# VSR_Mini_Mega_rev_1_206C_dual_led_option.net
KiCad netlist of a schematic drawn in EAGLE
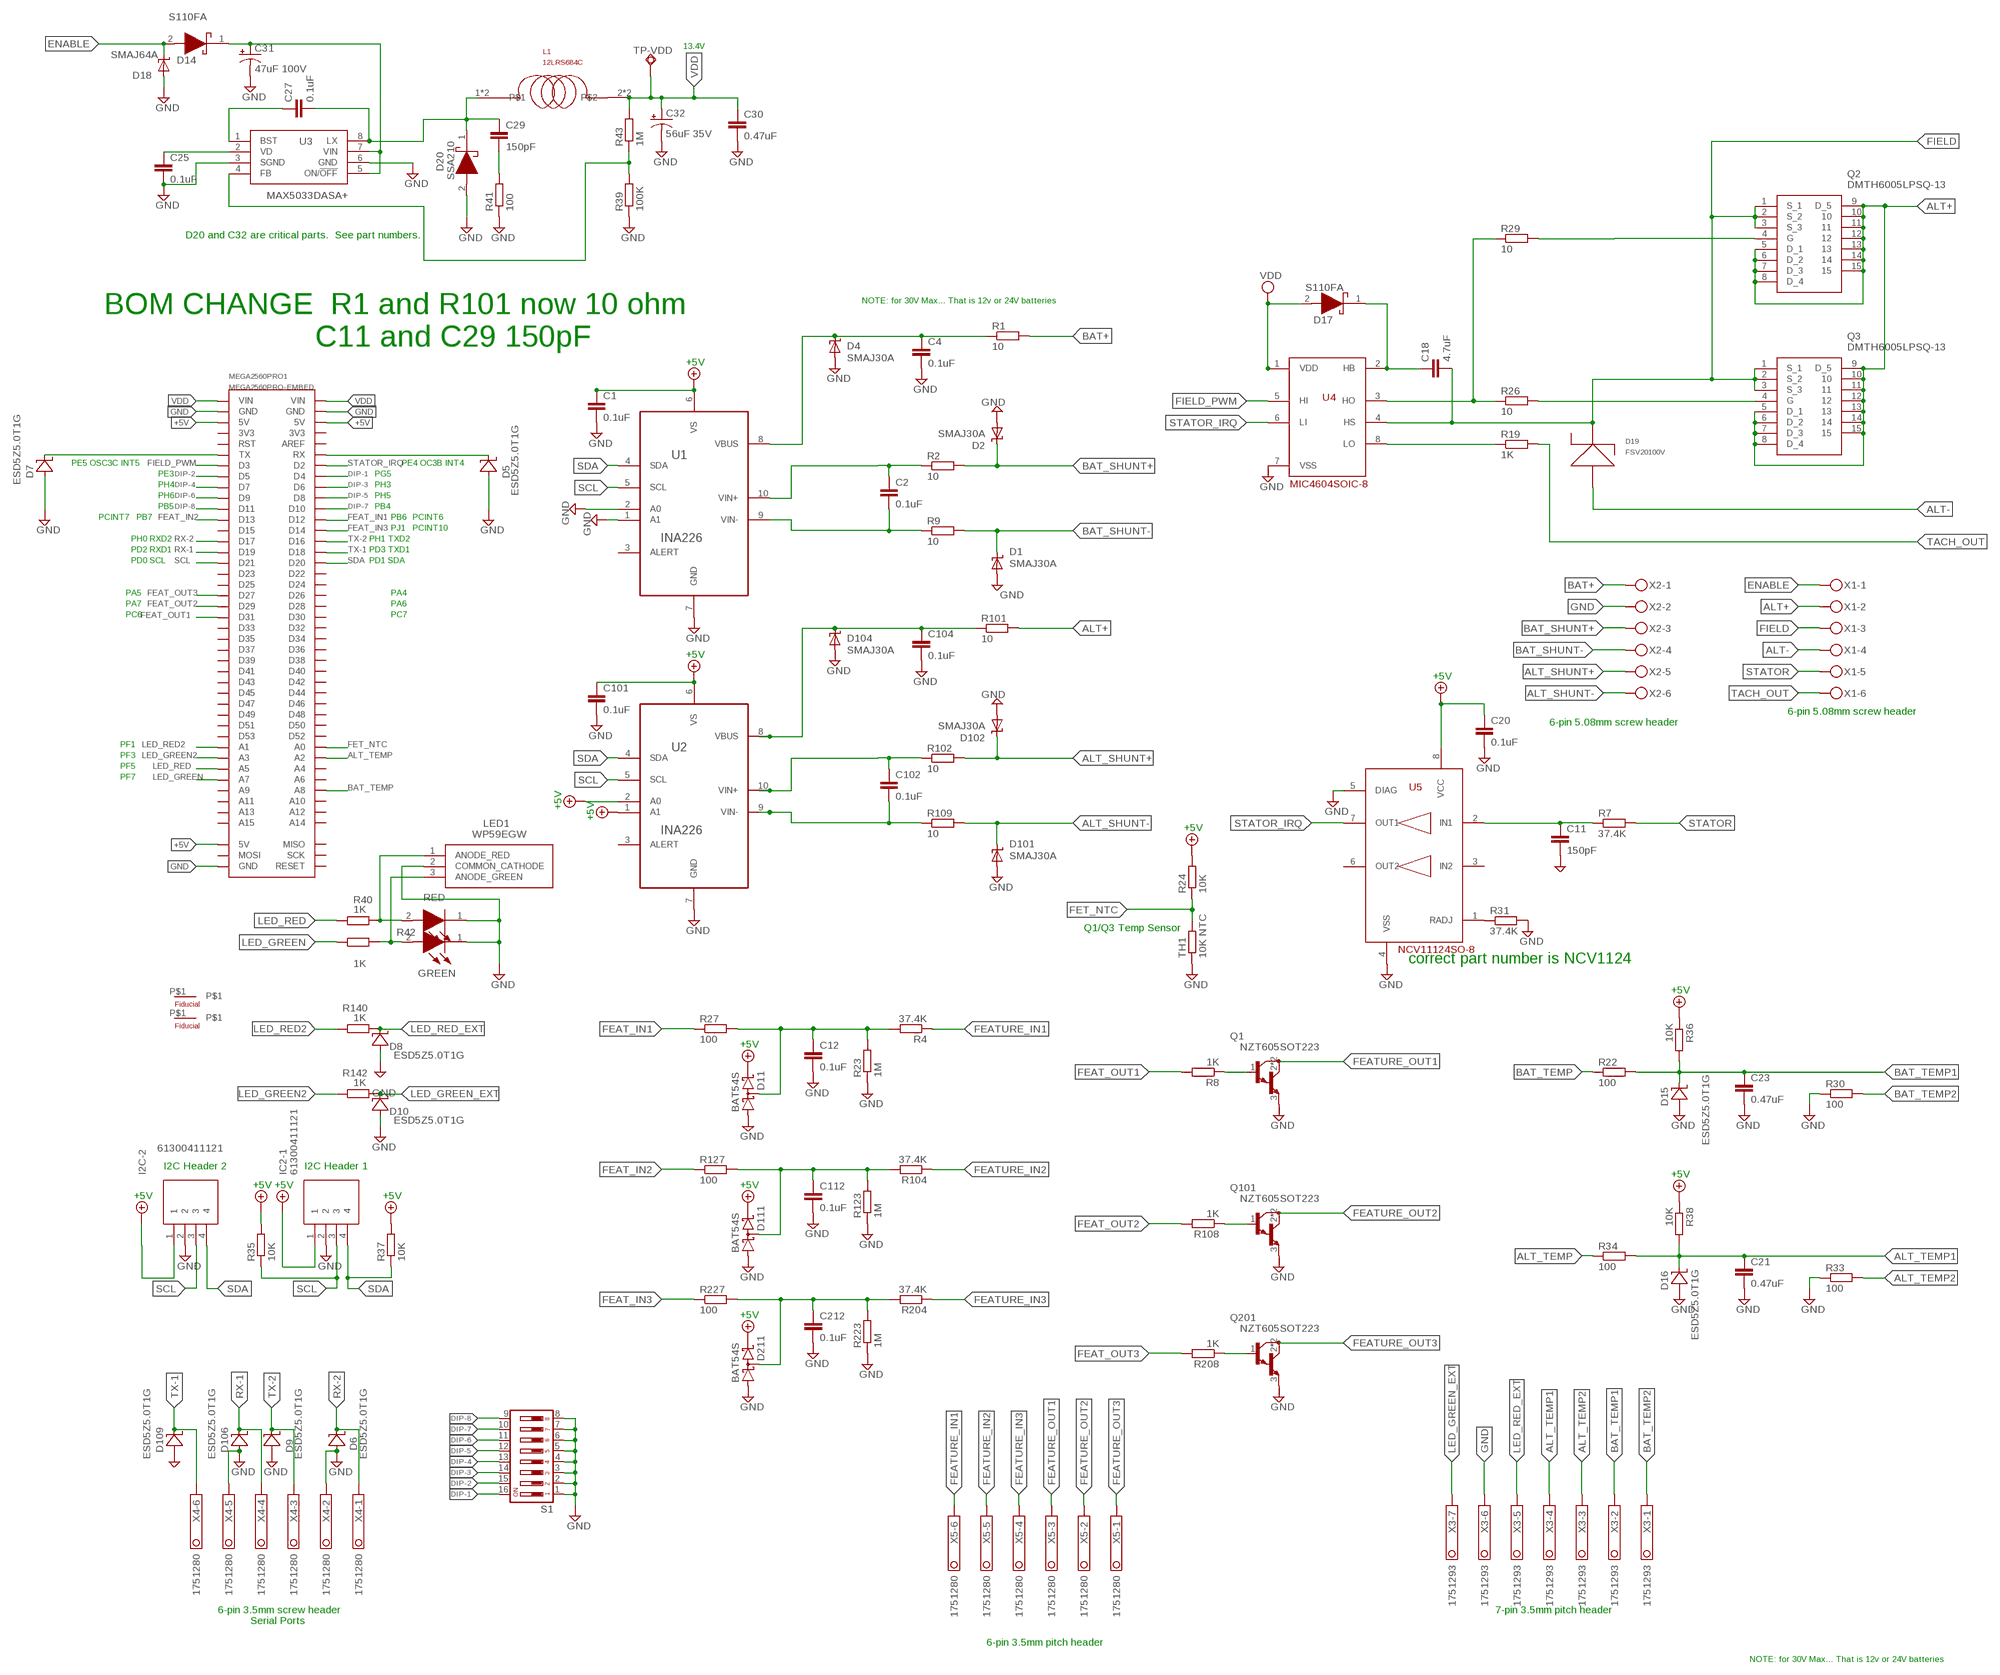
[diagram p0: schematic, sheet 1]

(export (version "E")
  (design (tool "Eeschema 10.0.6"))
  (components
    (comp (ref "C1")
      (value "0.1uF")
      (footprint "eagle-import:C0603")
      (libsource (lib "eagle-import") (part "C-EUC0603"))
    )
    (comp (ref "C2")
      (value "0.1uF")
      (footprint "eagle-import:C0603")
      (libsource (lib "eagle-import") (part "C-EUC0603"))
    )
    (comp (ref "C4")
      (value "0.1uF")
      (footprint "eagle-import:C0603")
      (libsource (lib "eagle-import") (part "C-EUC0603"))
    )
    (comp (ref "C11")
      (value "150pF")
      (footprint "eagle-import:C0603")
      (libsource (lib "eagle-import") (part "C-EUC0603"))
    )
    (comp (ref "C12")
      (value "0.1uF")
      (footprint "eagle-import:C0603")
      (libsource (lib "eagle-import") (part "C-EUC0603"))
    )
    (comp (ref "C18")
      (value "4.7uF")
      (footprint "eagle-import:C0603K")
      (libsource (lib "eagle-import") (part "C-EUC0603K"))
    )
    (comp (ref "C20")
      (value "0.1uF")
      (footprint "eagle-import:C0603")
      (libsource (lib "eagle-import") (part "C-EUC0603"))
    )
    (comp (ref "C21")
      (value "0.47uF")
      (footprint "eagle-import:C0603")
      (libsource (lib "eagle-import") (part "C-EUC0603"))
    )
    (comp (ref "C23")
      (value "0.47uF")
      (footprint "eagle-import:C0603")
      (libsource (lib "eagle-import") (part "C-EUC0603"))
    )
    (comp (ref "C25")
      (value "0.1uF")
      (footprint "eagle-import:C0603")
      (libsource (lib "eagle-import") (part "C-EUC0603"))
    )
    (comp (ref "C27")
      (value "0.1uF")
      (footprint "eagle-import:C0603")
      (libsource (lib "eagle-import") (part "C-EUC0603"))
    )
    (comp (ref "C29")
      (value "150pF")
      (footprint "eagle-import:C0603")
      (libsource (lib "eagle-import") (part "C-EUC0603"))
    )
    (comp (ref "C30")
      (value "0.47uF")
      (footprint "eagle-import:C0603")
      (libsource (lib "eagle-import") (part "C-EUC0603"))
    )
    (comp (ref "C31")
      (value "47uF 100V")
      (footprint "eagle-import:CAPPRD500W60D1000H1250B")
      (libsource (lib "eagle-import") (part "CPOL-USCAPPRD500W60D100H1250B"))
    )
    (comp (ref "C32")
      (value "56uF 35V")
      (footprint "eagle-import:CAPPRD250W50D630H1100B")
      (libsource (lib "eagle-import") (part "CPOL-US"))
    )
    (comp (ref "C101")
      (value "0.1uF")
      (footprint "eagle-import:C0603")
      (libsource (lib "eagle-import") (part "C-EUC0603"))
    )
    (comp (ref "C102")
      (value "0.1uF")
      (footprint "eagle-import:C0603")
      (libsource (lib "eagle-import") (part "C-EUC0603"))
    )
    (comp (ref "C104")
      (value "0.1uF")
      (footprint "eagle-import:C0603")
      (libsource (lib "eagle-import") (part "C-EUC0603"))
    )
    (comp (ref "C112")
      (value "0.1uF")
      (footprint "eagle-import:C0603")
      (libsource (lib "eagle-import") (part "C-EUC0603"))
    )
    (comp (ref "C212")
      (value "0.1uF")
      (footprint "eagle-import:C0603")
      (libsource (lib "eagle-import") (part "C-EUC0603"))
    )
    (comp (ref "D1")
      (value "SMAJ30A")
      (footprint "eagle-import:SMBJ")
      (libsource (lib "eagle-import") (part "SUPPRESSOR-SMBJ"))
    )
    (comp (ref "D2")
      (value "SMAJ30A")
      (footprint "eagle-import:SMBJ")
      (libsource (lib "eagle-import") (part "SUPPRESSOR-SMBJ"))
    )
    (comp (ref "D4")
      (value "SMAJ30A")
      (footprint "eagle-import:SMBJ")
      (libsource (lib "eagle-import") (part "SUPPRESSOR-SMBJ"))
    )
    (comp (ref "D5")
      (value "ESD5Z5.0T1G")
      (footprint "eagle-import:SOD523")
      (libsource (lib "eagle-import") (part "ESD5Z5.0T1G"))
    )
    (comp (ref "D6")
      (value "ESD5Z5.0T1G")
      (footprint "eagle-import:SOD523")
      (libsource (lib "eagle-import") (part "ESD5Z5.0T1G"))
    )
    (comp (ref "D7")
      (value "ESD5Z5.0T1G")
      (footprint "eagle-import:SOD523")
      (libsource (lib "eagle-import") (part "ESD5Z5.0T1G"))
    )
    (comp (ref "D8")
      (value "ESD5Z5.0T1G")
      (footprint "eagle-import:SOD523")
      (libsource (lib "eagle-import") (part "ESD5Z5.0T1G"))
    )
    (comp (ref "D9")
      (value "ESD5Z5.0T1G")
      (footprint "eagle-import:SOD523")
      (libsource (lib "eagle-import") (part "ESD5Z5.0T1G"))
    )
    (comp (ref "D10")
      (value "ESD5Z5.0T1G")
      (footprint "eagle-import:SOD523")
      (libsource (lib "eagle-import") (part "ESD5Z5.0T1G"))
    )
    (comp (ref "D11")
      (value "BAT54S")
      (footprint "eagle-import:SOT23")
      (libsource (lib "eagle-import") (part "BAT54S"))
    )
    (comp (ref "D14")
      (value "S110FA")
      (footprint "eagle-import:SODFL3618X143N")
      (fields (field (name "MOUSER_PART_NUMBER") "512-S110FA"))
      (libsource (lib "eagle-import") (part "S110FA"))
    )
    (comp (ref "D15")
      (value "ESD5Z5.0T1G")
      (footprint "eagle-import:SOD523")
      (libsource (lib "eagle-import") (part "ESD5Z5.0T1G"))
    )
    (comp (ref "D16")
      (value "ESD5Z5.0T1G")
      (footprint "eagle-import:SOD523")
      (libsource (lib "eagle-import") (part "ESD5Z5.0T1G"))
    )
    (comp (ref "D17")
      (value "S110FA")
      (footprint "eagle-import:SODFL3618X143N")
      (fields (field (name "MOUSER_PART_NUMBER") "512-S110FA"))
      (libsource (lib "eagle-import") (part "S110FA"))
    )
    (comp (ref "D18")
      (value "SMAJ64A")
      (footprint "eagle-import:SMBJ")
      (libsource (lib "eagle-import") (part "SUPPRESSOR-SMBJ"))
    )
    (comp (ref "D19")
      (value "FSV20100V")
      (footprint "eagle-import:TO-277")
      (fields (field (name "MF") "ON Semiconductor"))
      (libsource (lib "eagle-import") (part "FSV20100V"))
    )
    (comp (ref "D20")
      (value "SSA210")
      (footprint "eagle-import:DIOM5227X270N")
      (fields (field (name "MOUSER_PART_NUMBER") "512-SSA210"))
      (libsource (lib "eagle-import") (part "SSA210"))
    )
    (comp (ref "D101")
      (value "SMAJ30A")
      (footprint "eagle-import:SMBJ")
      (libsource (lib "eagle-import") (part "SUPPRESSOR-SMBJ"))
    )
    (comp (ref "D102")
      (value "SMAJ30A")
      (footprint "eagle-import:SMBJ")
      (libsource (lib "eagle-import") (part "SUPPRESSOR-SMBJ"))
    )
    (comp (ref "D104")
      (value "SMAJ30A")
      (footprint "eagle-import:SMBJ")
      (libsource (lib "eagle-import") (part "SUPPRESSOR-SMBJ"))
    )
    (comp (ref "D106")
      (value "ESD5Z5.0T1G")
      (footprint "eagle-import:SOD523")
      (libsource (lib "eagle-import") (part "ESD5Z5.0T1G"))
    )
    (comp (ref "D109")
      (value "ESD5Z5.0T1G")
      (footprint "eagle-import:SOD523")
      (libsource (lib "eagle-import") (part "ESD5Z5.0T1G"))
    )
    (comp (ref "D111")
      (value "BAT54S")
      (footprint "eagle-import:SOT23")
      (libsource (lib "eagle-import") (part "BAT54S"))
    )
    (comp (ref "D211")
      (value "BAT54S")
      (footprint "eagle-import:SOT23")
      (libsource (lib "eagle-import") (part "BAT54S"))
    )
    (comp (ref "FIDUCIAL1")
      (value "FIDUCIAL060")
      (footprint "eagle-import:FIDUCIAL060")
      (libsource (lib "eagle-import") (part "FIDUCIAL060"))
    )
    (comp (ref "FIDUCIAL2")
      (value "FIDUCIAL060")
      (footprint "eagle-import:FIDUCIAL060")
      (libsource (lib "eagle-import") (part "FIDUCIAL060"))
    )
    (comp (ref "GREEN")
      (value "599-0110-007F")
      (footprint "eagle-import:LEDM2012X90N")
      (fields (field (name "MOUSER_PART_NUMBER") "645-599-0110-007F"))
      (libsource (lib "eagle-import") (part "599-0110-007F"))
    )
    (comp (ref "I2C-2")
      (value "61300411121")
      (footprint "eagle-import:HDRV4W95P0X254_1X4_1016X254X85")
      (fields (field (name "MOUSER_PART_NUMBER") "710-61300411121"))
      (libsource (lib "eagle-import") (part "61300411121"))
    )
    (comp (ref "IC2-1")
      (value "61300411121")
      (footprint "eagle-import:HDRV4W95P0X254_1X4_1016X254X85")
      (fields (field (name "MOUSER_PART_NUMBER") "710-61300411121"))
      (libsource (lib "eagle-import") (part "61300411121"))
    )
    (comp (ref "L1")
      (value "12LRS684C")
      (footprint "eagle-import:IND_12LRS156C")
      (libsource (lib "eagle-import") (part "12LRS684C"))
    )
    (comp (ref "LED1")
      (value "WP59EGW")
      (footprint "eagle-import:T-1_3_4(5MM)_BI-COLOR_INDICATO")
      (fields (field (name "MOUSER_PART_NUMBER") "604-WP59EGW"))
      (libsource (lib "eagle-import") (part "WP59EGW"))
    )
    (comp (ref "MEGA2560PRO1")
      (value "MEGA2560PRO-EMBED")
      (footprint "eagle-import:MEGA2560PRO-EMBED")
      (libsource (lib "eagle-import") (part "MEGA2560PRO-EMBED"))
    )
    (comp (ref "Q1")
      (value "NZT605SOT223")
      (footprint "eagle-import:SOT223")
      (libsource (lib "eagle-import") (part "NZT605SOT223"))
    )
    (comp (ref "Q2")
      (value "DMTH6005LPSQ-13")
      (footprint "eagle-import:DMTH6005LPSQ13")
      (fields (field (name "MOUSER_PART_NUMBER") "621-DMTH6005LPSQ-13"))
      (libsource (lib "eagle-import") (part "DMTH6005LPSQ-13"))
    )
    (comp (ref "Q3")
      (value "DMTH6005LPSQ-13")
      (footprint "eagle-import:DMTH6005LPSQ13")
      (fields (field (name "MOUSER_PART_NUMBER") "621-DMTH6005LPSQ-13"))
      (libsource (lib "eagle-import") (part "DMTH6005LPSQ-13"))
    )
    (comp (ref "Q101")
      (value "NZT605SOT223")
      (footprint "eagle-import:SOT223")
      (libsource (lib "eagle-import") (part "NZT605SOT223"))
    )
    (comp (ref "Q201")
      (value "NZT605SOT223")
      (footprint "eagle-import:SOT223")
      (libsource (lib "eagle-import") (part "NZT605SOT223"))
    )
    (comp (ref "R1")
      (value "10")
      (footprint "eagle-import:R0603")
      (libsource (lib "eagle-import") (part "R-EU_R0603"))
    )
    (comp (ref "R2")
      (value "10")
      (footprint "eagle-import:R0603")
      (libsource (lib "eagle-import") (part "R-EU_R0603"))
    )
    (comp (ref "R4")
      (value "37.4K")
      (footprint "eagle-import:R0603")
      (libsource (lib "eagle-import") (part "R-EU_R0603"))
    )
    (comp (ref "R7")
      (value "37.4K")
      (footprint "eagle-import:R0603")
      (libsource (lib "eagle-import") (part "R-EU_R0603"))
    )
    (comp (ref "R8")
      (value "1K")
      (footprint "eagle-import:R0603")
      (libsource (lib "eagle-import") (part "R-EU_R0603"))
    )
    (comp (ref "R9")
      (value "10")
      (footprint "eagle-import:R0603")
      (libsource (lib "eagle-import") (part "R-EU_R0603"))
    )
    (comp (ref "R19")
      (value "1K")
      (footprint "eagle-import:R0603")
      (libsource (lib "eagle-import") (part "R-EU_R0603"))
    )
    (comp (ref "R22")
      (value "100")
      (footprint "eagle-import:R0603")
      (libsource (lib "eagle-import") (part "R-EU_R0603"))
    )
    (comp (ref "R23")
      (value "1M")
      (footprint "eagle-import:R0603")
      (libsource (lib "eagle-import") (part "R-EU_R0603"))
    )
    (comp (ref "R24")
      (value "10K")
      (footprint "eagle-import:R0603")
      (libsource (lib "eagle-import") (part "R-EU_R0603"))
    )
    (comp (ref "R26")
      (value "10")
      (footprint "eagle-import:R0603")
      (libsource (lib "eagle-import") (part "R-EU_R0603"))
    )
    (comp (ref "R27")
      (value "100")
      (footprint "eagle-import:R0603")
      (libsource (lib "eagle-import") (part "R-EU_R0603"))
    )
    (comp (ref "R29")
      (value "10")
      (footprint "eagle-import:R0603")
      (libsource (lib "eagle-import") (part "R-EU_R0603"))
    )
    (comp (ref "R30")
      (value "100")
      (footprint "eagle-import:R0603")
      (libsource (lib "eagle-import") (part "R-EU_R0603"))
    )
    (comp (ref "R31")
      (value "37.4K")
      (footprint "eagle-import:R0603")
      (libsource (lib "eagle-import") (part "R-EU_R0603"))
    )
    (comp (ref "R33")
      (value "100")
      (footprint "eagle-import:R0603")
      (libsource (lib "eagle-import") (part "R-EU_R0603"))
    )
    (comp (ref "R34")
      (value "100")
      (footprint "eagle-import:R0603")
      (libsource (lib "eagle-import") (part "R-EU_R0603"))
    )
    (comp (ref "R35")
      (value "10K")
      (footprint "eagle-import:R0603")
      (libsource (lib "eagle-import") (part "R-EU_R0603"))
    )
    (comp (ref "R36")
      (value "10K")
      (footprint "eagle-import:R0603")
      (libsource (lib "eagle-import") (part "R-EU_R0603"))
    )
    (comp (ref "R37")
      (value "10K")
      (footprint "eagle-import:R0603")
      (libsource (lib "eagle-import") (part "R-EU_R0603"))
    )
    (comp (ref "R38")
      (value "10K")
      (footprint "eagle-import:R0603")
      (libsource (lib "eagle-import") (part "R-EU_R0603"))
    )
    (comp (ref "R39")
      (value "100K")
      (footprint "eagle-import:R0603")
      (libsource (lib "eagle-import") (part "R-EU_R0603"))
    )
    (comp (ref "R40")
      (value "1K")
      (footprint "eagle-import:R0603")
      (libsource (lib "eagle-import") (part "R-EU_R0603"))
    )
    (comp (ref "R41")
      (value "100")
      (footprint "eagle-import:R0603")
      (libsource (lib "eagle-import") (part "R-EU_R0603"))
    )
    (comp (ref "R42")
      (value "1K")
      (footprint "eagle-import:R0603")
      (libsource (lib "eagle-import") (part "R-EU_R0603"))
    )
    (comp (ref "R43")
      (value "1M")
      (footprint "eagle-import:R0603")
      (libsource (lib "eagle-import") (part "R-EU_R0603"))
    )
    (comp (ref "R101")
      (value "10")
      (footprint "eagle-import:R0603")
      (libsource (lib "eagle-import") (part "R-EU_R0603"))
    )
    (comp (ref "R102")
      (value "10")
      (footprint "eagle-import:R0603")
      (libsource (lib "eagle-import") (part "R-EU_R0603"))
    )
    (comp (ref "R104")
      (value "37.4K")
      (footprint "eagle-import:R0603")
      (libsource (lib "eagle-import") (part "R-EU_R0603"))
    )
    (comp (ref "R108")
      (value "1K")
      (footprint "eagle-import:R0603")
      (libsource (lib "eagle-import") (part "R-EU_R0603"))
    )
    (comp (ref "R109")
      (value "10")
      (footprint "eagle-import:R0603")
      (libsource (lib "eagle-import") (part "R-EU_R0603"))
    )
    (comp (ref "R123")
      (value "1M")
      (footprint "eagle-import:R0603")
      (libsource (lib "eagle-import") (part "R-EU_R0603"))
    )
    (comp (ref "R127")
      (value "100")
      (footprint "eagle-import:R0603")
      (libsource (lib "eagle-import") (part "R-EU_R0603"))
    )
    (comp (ref "R140")
      (value "1K")
      (footprint "eagle-import:R0603")
      (libsource (lib "eagle-import") (part "R-EU_R0603"))
    )
    (comp (ref "R142")
      (value "1K")
      (footprint "eagle-import:R0603")
      (libsource (lib "eagle-import") (part "R-EU_R0603"))
    )
    (comp (ref "R204")
      (value "37.4K")
      (footprint "eagle-import:R0603")
      (libsource (lib "eagle-import") (part "R-EU_R0603"))
    )
    (comp (ref "R208")
      (value "1K")
      (footprint "eagle-import:R0603")
      (libsource (lib "eagle-import") (part "R-EU_R0603"))
    )
    (comp (ref "R223")
      (value "1M")
      (footprint "eagle-import:R0603")
      (libsource (lib "eagle-import") (part "R-EU_R0603"))
    )
    (comp (ref "R227")
      (value "100")
      (footprint "eagle-import:R0603")
      (libsource (lib "eagle-import") (part "R-EU_R0603"))
    )
    (comp (ref "RED")
      (value "599-0110-007F")
      (footprint "eagle-import:LEDM2012X90N")
      (fields (field (name "MOUSER_PART_NUMBER") "645-599-0110-007F"))
      (libsource (lib "eagle-import") (part "599-0110-007F"))
    )
    (comp (ref "S1")
      (value "DP08")
      (footprint "eagle-import:DP-08")
      (libsource (lib "eagle-import") (part "DP08"))
    )
    (comp (ref "TH1")
      (value "10K NTC")
      (footprint "eagle-import:R0402")
      (libsource (lib "eagle-import") (part "R-EU_R0402"))
    )
    (comp (ref "TP-VDD")
      (value "TPSQTP20SQ")
      (footprint "eagle-import:TP20SQ")
      (libsource (lib "eagle-import") (part "TPSQTP20SQ"))
    )
    (comp (ref "U1")
      (value "INA226")
      (footprint "eagle-import:SOP50P490X110-10N")
      (fields (field (name "MPN") "INA226AIDGSR"))
      (libsource (lib "eagle-import") (part "INA226"))
    )
    (comp (ref "U2")
      (value "INA226")
      (footprint "eagle-import:SOP50P490X110-10N")
      (fields (field (name "MPN") "INA226AIDGSR"))
      (libsource (lib "eagle-import") (part "INA226"))
    )
    (comp (ref "U3")
      (value "MAX5033DASA+")
      (footprint "eagle-import:SOIC127P600X175-8N")
      (fields (field (name "MOUSER_PART_NUMBER") "700-MAX5033DASA"))
      (libsource (lib "eagle-import") (part "MAX5033DASA+"))
    )
    (comp (ref "U4")
      (value "MIC4604SOIC-8")
      (footprint "eagle-import:SOIC8")
      (libsource (lib "eagle-import") (part "MIC4604SOIC-8"))
    )
    (comp (ref "U5")
      (value "NCV11124SO-8")
      (footprint "eagle-import:SO-8")
      (libsource (lib "eagle-import") (part "NCV11124SO-8"))
    )
    (comp (ref "X1")
      (value "MKDSN1,5/6-5,08")
      (footprint "eagle-import:MKDSN1,5_6-5,08")
      (libsource (lib "eagle-import") (part "MKDSN1,5/6-5,08"))
    )
    (comp (ref "X2")
      (value "MKDSN1,5/6-5,08")
      (footprint "eagle-import:MKDSN1,5_6-5,08")
      (libsource (lib "eagle-import") (part "MKDSN1,5/6-5,08"))
    )
    (comp (ref "X3")
      (value "1751293")
      (footprint "eagle-import:1751293")
      (libsource (lib "eagle-import") (part "1751293"))
    )
    (comp (ref "X4")
      (value "1751280")
      (footprint "eagle-import:1751280")
      (libsource (lib "eagle-import") (part "1751280"))
    )
    (comp (ref "X5")
      (value "1751280")
      (footprint "eagle-import:1751280")
      (libsource (lib "eagle-import") (part "1751280"))
    )
  )
  (nets
    (net (code "1") (name "+5V") (class "Default")
      (node (ref "C1") (pin "1") (pinfunction "1_1") (pintype "passive"))
      (node (ref "C101") (pin "1") (pinfunction "1_1") (pintype "passive"))
      (node (ref "C20") (pin "1") (pinfunction "1_1") (pintype "passive"))
      (node (ref "D11") (pin "2") (pinfunction "C2_2") (pintype "passive"))
      (node (ref "D111") (pin "2") (pinfunction "C2_2") (pintype "passive"))
      (node (ref "D211") (pin "2") (pinfunction "C2_2") (pintype "passive"))
      (node (ref "I2C-2") (pin "1") (pinfunction "1_1") (pintype "bidirectional"))
      (node (ref "IC2-1") (pin "1") (pinfunction "1_1") (pintype "bidirectional"))
      (node (ref "MEGA2560PRO1") (pin "5V@1") (pinfunction "5V_5V@1") (pintype "bidirectional"))
      (node (ref "MEGA2560PRO1") (pin "5V@2") (pinfunction "5V_5V@2") (pintype "bidirectional"))
      (node (ref "MEGA2560PRO1") (pin "5V@3") (pinfunction "5V_5V@3") (pintype "bidirectional"))
      (node (ref "R24") (pin "2") (pinfunction "2_2") (pintype "passive"))
      (node (ref "R35") (pin "2") (pinfunction "2_2") (pintype "passive"))
      (node (ref "R36") (pin "1") (pinfunction "1_1") (pintype "passive"))
      (node (ref "R37") (pin "2") (pinfunction "2_2") (pintype "passive"))
      (node (ref "R38") (pin "1") (pinfunction "1_1") (pintype "passive"))
      (node (ref "U1") (pin "6") (pinfunction "VS_6") (pintype "power_in"))
      (node (ref "U2") (pin "1") (pinfunction "A1_1") (pintype "input"))
      (node (ref "U2") (pin "2") (pinfunction "A0_2") (pintype "input"))
      (node (ref "U2") (pin "6") (pinfunction "VS_6") (pintype "power_in"))
      (node (ref "U5") (pin "8") (pinfunction "VCC_8") (pintype "bidirectional"))
    )
    (net (code "2") (name "ALT+") (class "Default")
      (node (ref "Q2") (pin "10") (pinfunction "10_10") (pintype "bidirectional"))
      (node (ref "Q2") (pin "11") (pinfunction "11_11") (pintype "bidirectional"))
      (node (ref "Q2") (pin "12") (pinfunction "12_12") (pintype "bidirectional"))
      (node (ref "Q2") (pin "13") (pinfunction "13_13") (pintype "bidirectional"))
      (node (ref "Q2") (pin "14") (pinfunction "14_14") (pintype "bidirectional"))
      (node (ref "Q2") (pin "15") (pinfunction "15_15") (pintype "bidirectional"))
      (node (ref "Q2") (pin "5") (pinfunction "D_1_5") (pintype "bidirectional"))
      (node (ref "Q2") (pin "6") (pinfunction "D_2_6") (pintype "bidirectional"))
      (node (ref "Q2") (pin "7") (pinfunction "D_3_7") (pintype "bidirectional"))
      (node (ref "Q2") (pin "8") (pinfunction "D_4_8") (pintype "bidirectional"))
      (node (ref "Q2") (pin "9") (pinfunction "D_5_9") (pintype "bidirectional"))
      (node (ref "Q3") (pin "10") (pinfunction "10_10") (pintype "bidirectional"))
      (node (ref "Q3") (pin "11") (pinfunction "11_11") (pintype "bidirectional"))
      (node (ref "Q3") (pin "12") (pinfunction "12_12") (pintype "bidirectional"))
      (node (ref "Q3") (pin "13") (pinfunction "13_13") (pintype "bidirectional"))
      (node (ref "Q3") (pin "14") (pinfunction "14_14") (pintype "bidirectional"))
      (node (ref "Q3") (pin "15") (pinfunction "15_15") (pintype "bidirectional"))
      (node (ref "Q3") (pin "5") (pinfunction "D_1_5") (pintype "bidirectional"))
      (node (ref "Q3") (pin "6") (pinfunction "D_2_6") (pintype "bidirectional"))
      (node (ref "Q3") (pin "7") (pinfunction "D_3_7") (pintype "bidirectional"))
      (node (ref "Q3") (pin "8") (pinfunction "D_4_8") (pintype "bidirectional"))
      (node (ref "Q3") (pin "9") (pinfunction "D_5_9") (pintype "bidirectional"))
      (node (ref "R101") (pin "2") (pinfunction "2_2") (pintype "passive"))
      (node (ref "X1") (pin "2") (pinfunction "KL_2") (pintype "passive"))
    )
    (net (code "3") (name "ALT-") (class "Default")
      (node (ref "D19") (pin "1") (pinfunction "P$2_1") (pintype "bidirectional"))
      (node (ref "D19") (pin "2") (pinfunction "P$2_2") (pintype "bidirectional"))
      (node (ref "X1") (pin "4") (pinfunction "KL_4") (pintype "passive"))
    )
    (net (code "4") (name "ALT_SHUNT+") (class "Default")
      (node (ref "D102") (pin "C") (pinfunction "C_C") (pintype "passive"))
      (node (ref "R102") (pin "2") (pinfunction "2_2") (pintype "passive"))
      (node (ref "X2") (pin "5") (pinfunction "KL_5") (pintype "passive"))
    )
    (net (code "5") (name "ALT_SHUNT-") (class "Default")
      (node (ref "D101") (pin "C") (pinfunction "C_C") (pintype "passive"))
      (node (ref "R109") (pin "2") (pinfunction "2_2") (pintype "passive"))
      (node (ref "X2") (pin "6") (pinfunction "KL_6") (pintype "passive"))
    )
    (net (code "6") (name "ALT_TEMP") (class "Default")
      (node (ref "MEGA2560PRO1") (pin "A2") (pinfunction "A2_A2") (pintype "bidirectional"))
      (node (ref "R34") (pin "1") (pinfunction "1_1") (pintype "passive"))
    )
    (net (code "7") (name "ALT_TEMP1") (class "Default")
      (node (ref "C21") (pin "1") (pinfunction "1_1") (pintype "passive"))
      (node (ref "D16") (pin "C") (pinfunction "C_C") (pintype "passive"))
      (node (ref "R34") (pin "2") (pinfunction "2_2") (pintype "passive"))
      (node (ref "R38") (pin "2") (pinfunction "2_2") (pintype "passive"))
      (node (ref "X3") (pin "4") (pinfunction "K_4") (pintype "passive"))
    )
    (net (code "8") (name "ALT_TEMP2") (class "Default")
      (node (ref "R33") (pin "2") (pinfunction "2_2") (pintype "passive"))
      (node (ref "X3") (pin "3") (pinfunction "K_3") (pintype "passive"))
    )
    (net (code "9") (name "BAT+") (class "Default")
      (node (ref "R1") (pin "2") (pinfunction "2_2") (pintype "passive"))
      (node (ref "X2") (pin "1") (pinfunction "KL_1") (pintype "passive"))
    )
    (net (code "10") (name "BAT_SHUNT+") (class "Default")
      (node (ref "D2") (pin "C") (pinfunction "C_C") (pintype "passive"))
      (node (ref "R2") (pin "2") (pinfunction "2_2") (pintype "passive"))
      (node (ref "X2") (pin "3") (pinfunction "KL_3") (pintype "passive"))
    )
    (net (code "11") (name "BAT_SHUNT-") (class "Default")
      (node (ref "D1") (pin "C") (pinfunction "C_C") (pintype "passive"))
      (node (ref "R9") (pin "2") (pinfunction "2_2") (pintype "passive"))
      (node (ref "X2") (pin "4") (pinfunction "KL_4") (pintype "passive"))
    )
    (net (code "12") (name "BAT_TEMP") (class "Default")
      (node (ref "MEGA2560PRO1") (pin "A8") (pinfunction "A8_A8") (pintype "bidirectional"))
      (node (ref "R22") (pin "1") (pinfunction "1_1") (pintype "passive"))
    )
    (net (code "13") (name "BAT_TEMP1") (class "Default")
      (node (ref "C23") (pin "1") (pinfunction "1_1") (pintype "passive"))
      (node (ref "D15") (pin "C") (pinfunction "C_C") (pintype "passive"))
      (node (ref "R22") (pin "2") (pinfunction "2_2") (pintype "passive"))
      (node (ref "R36") (pin "2") (pinfunction "2_2") (pintype "passive"))
      (node (ref "X3") (pin "2") (pinfunction "K_2") (pintype "passive"))
    )
    (net (code "14") (name "BAT_TEMP2") (class "Default")
      (node (ref "R30") (pin "2") (pinfunction "2_2") (pintype "passive"))
      (node (ref "X3") (pin "1") (pinfunction "K_1") (pintype "passive"))
    )
    (net (code "15") (name "DIP-1") (class "Default")
      (node (ref "MEGA2560PRO1") (pin "D4") (pinfunction "D4_D4") (pintype "bidirectional"))
      (node (ref "S1") (pin "16") (pinfunction "16_16") (pintype "passive"))
    )
    (net (code "16") (name "DIP-2") (class "Default")
      (node (ref "MEGA2560PRO1") (pin "D5") (pinfunction "D5_D5") (pintype "bidirectional"))
      (node (ref "S1") (pin "15") (pinfunction "15_15") (pintype "passive"))
    )
    (net (code "17") (name "DIP-3") (class "Default")
      (node (ref "MEGA2560PRO1") (pin "D6") (pinfunction "D6_D6") (pintype "bidirectional"))
      (node (ref "S1") (pin "14") (pinfunction "14_14") (pintype "passive"))
    )
    (net (code "18") (name "DIP-4") (class "Default")
      (node (ref "MEGA2560PRO1") (pin "D7") (pinfunction "D7_D7") (pintype "bidirectional"))
      (node (ref "S1") (pin "13") (pinfunction "13_13") (pintype "passive"))
    )
    (net (code "19") (name "DIP-5") (class "Default")
      (node (ref "MEGA2560PRO1") (pin "D8") (pinfunction "D8_D8") (pintype "bidirectional"))
      (node (ref "S1") (pin "12") (pinfunction "12_12") (pintype "passive"))
    )
    (net (code "20") (name "DIP-6") (class "Default")
      (node (ref "MEGA2560PRO1") (pin "D9") (pinfunction "D9_D9") (pintype "bidirectional"))
      (node (ref "S1") (pin "11") (pinfunction "11_11") (pintype "passive"))
    )
    (net (code "21") (name "DIP-7") (class "Default")
      (node (ref "MEGA2560PRO1") (pin "D10") (pinfunction "D10_D10") (pintype "bidirectional"))
      (node (ref "S1") (pin "10") (pinfunction "10_10") (pintype "passive"))
    )
    (net (code "22") (name "DIP-8") (class "Default")
      (node (ref "MEGA2560PRO1") (pin "D11") (pinfunction "D11_D11") (pintype "bidirectional"))
      (node (ref "S1") (pin "9") (pinfunction "9_9") (pintype "passive"))
    )
    (net (code "23") (name "ENABLE") (class "Default")
      (node (ref "D14") (pin "2") (pinfunction "A_2") (pintype "bidirectional"))
      (node (ref "D18") (pin "C") (pinfunction "C_C") (pintype "passive"))
      (node (ref "X1") (pin "1") (pinfunction "KL_1") (pintype "passive"))
    )
    (net (code "24") (name "FEATURE_IN1") (class "Default")
      (node (ref "R4") (pin "1") (pinfunction "1_1") (pintype "passive"))
      (node (ref "X5") (pin "6") (pinfunction "K_6") (pintype "passive"))
    )
    (net (code "25") (name "FEATURE_IN2") (class "Default")
      (node (ref "R104") (pin "1") (pinfunction "1_1") (pintype "passive"))
      (node (ref "X5") (pin "5") (pinfunction "K_5") (pintype "passive"))
    )
    (net (code "26") (name "FEATURE_IN3") (class "Default")
      (node (ref "R204") (pin "1") (pinfunction "1_1") (pintype "passive"))
      (node (ref "X5") (pin "4") (pinfunction "K_4") (pintype "passive"))
    )
    (net (code "27") (name "FEATURE_OUT1") (class "Default")
      (node (ref "Q1") (pin "2") (pinfunction "C_2") (pintype "passive"))
      (node (ref "Q1") (pin "4") (pinfunction "C_4") (pintype "passive"))
      (node (ref "X5") (pin "3") (pinfunction "K_3") (pintype "passive"))
    )
    (net (code "28") (name "FEATURE_OUT2") (class "Default")
      (node (ref "Q101") (pin "2") (pinfunction "C_2") (pintype "passive"))
      (node (ref "Q101") (pin "4") (pinfunction "C_4") (pintype "passive"))
      (node (ref "X5") (pin "2") (pinfunction "K_2") (pintype "passive"))
    )
    (net (code "29") (name "FEATURE_OUT3") (class "Default")
      (node (ref "Q201") (pin "2") (pinfunction "C_2") (pintype "passive"))
      (node (ref "Q201") (pin "4") (pinfunction "C_4") (pintype "passive"))
      (node (ref "X5") (pin "1") (pinfunction "K_1") (pintype "passive"))
    )
    (net (code "30") (name "FEAT_IN1") (class "Default")
      (node (ref "MEGA2560PRO1") (pin "D12") (pinfunction "D12_D12") (pintype "bidirectional"))
      (node (ref "R27") (pin "1") (pinfunction "1_1") (pintype "passive"))
    )
    (net (code "31") (name "FEAT_IN2") (class "Default")
      (node (ref "MEGA2560PRO1") (pin "D13") (pinfunction "D13_D13") (pintype "bidirectional"))
      (node (ref "R127") (pin "1") (pinfunction "1_1") (pintype "passive"))
    )
    (net (code "32") (name "FEAT_IN3") (class "Default")
      (node (ref "MEGA2560PRO1") (pin "D14") (pinfunction "D14_D14") (pintype "bidirectional"))
      (node (ref "R227") (pin "1") (pinfunction "1_1") (pintype "passive"))
    )
    (net (code "33") (name "FEAT_OUT1") (class "Default")
      (node (ref "MEGA2560PRO1") (pin "D31") (pinfunction "D31_D31") (pintype "bidirectional"))
      (node (ref "R8") (pin "2") (pinfunction "2_2") (pintype "passive"))
    )
    (net (code "34") (name "FEAT_OUT2") (class "Default")
      (node (ref "MEGA2560PRO1") (pin "D29") (pinfunction "D29_D29") (pintype "bidirectional"))
      (node (ref "R108") (pin "2") (pinfunction "2_2") (pintype "passive"))
    )
    (net (code "35") (name "FEAT_OUT3") (class "Default")
      (node (ref "MEGA2560PRO1") (pin "D27") (pinfunction "D27_D27") (pintype "bidirectional"))
      (node (ref "R208") (pin "2") (pinfunction "2_2") (pintype "passive"))
    )
    (net (code "36") (name "FET_NTC") (class "Default")
      (node (ref "MEGA2560PRO1") (pin "A0") (pinfunction "A0_A0") (pintype "bidirectional"))
      (node (ref "R24") (pin "1") (pinfunction "1_1") (pintype "passive"))
      (node (ref "TH1") (pin "2") (pinfunction "2_2") (pintype "passive"))
    )
    (net (code "37") (name "FIELD") (class "Default")
      (node (ref "C18") (pin "2") (pinfunction "2_2") (pintype "passive"))
      (node (ref "D19") (pin "3") (pinfunction "P$1_3") (pintype "bidirectional"))
      (node (ref "Q2") (pin "1") (pinfunction "S_1_1") (pintype "bidirectional"))
      (node (ref "Q2") (pin "2") (pinfunction "S_2_2") (pintype "bidirectional"))
      (node (ref "Q2") (pin "3") (pinfunction "S_3_3") (pintype "bidirectional"))
      (node (ref "Q3") (pin "1") (pinfunction "S_1_1") (pintype "bidirectional"))
      (node (ref "Q3") (pin "2") (pinfunction "S_2_2") (pintype "bidirectional"))
      (node (ref "Q3") (pin "3") (pinfunction "S_3_3") (pintype "bidirectional"))
      (node (ref "U4") (pin "4") (pinfunction "HS_4") (pintype "bidirectional"))
      (node (ref "X1") (pin "3") (pinfunction "KL_3") (pintype "passive"))
    )
    (net (code "38") (name "FIELD_PWM") (class "Default")
      (node (ref "MEGA2560PRO1") (pin "D3") (pinfunction "D3_D3") (pintype "bidirectional"))
      (node (ref "U4") (pin "5") (pinfunction "HI_5") (pintype "bidirectional"))
    )
    (net (code "39") (name "GND") (class "Default")
      (node (ref "C1") (pin "2") (pinfunction "2_2") (pintype "passive"))
      (node (ref "C101") (pin "2") (pinfunction "2_2") (pintype "passive"))
      (node (ref "C104") (pin "2") (pinfunction "2_2") (pintype "passive"))
      (node (ref "C11") (pin "2") (pinfunction "2_2") (pintype "passive"))
      (node (ref "C112") (pin "2") (pinfunction "2_2") (pintype "passive"))
      (node (ref "C12") (pin "2") (pinfunction "2_2") (pintype "passive"))
      (node (ref "C20") (pin "2") (pinfunction "2_2") (pintype "passive"))
      (node (ref "C21") (pin "2") (pinfunction "2_2") (pintype "passive"))
      (node (ref "C212") (pin "2") (pinfunction "2_2") (pintype "passive"))
      (node (ref "C23") (pin "2") (pinfunction "2_2") (pintype "passive"))
      (node (ref "C25") (pin "2") (pinfunction "2_2") (pintype "passive"))
      (node (ref "C30") (pin "2") (pinfunction "2_2") (pintype "passive"))
      (node (ref "C31") (pin "2") (pinfunction "-_2") (pintype "passive"))
      (node (ref "C32") (pin "2") (pinfunction "-_2") (pintype "passive"))
      (node (ref "C4") (pin "2") (pinfunction "2_2") (pintype "passive"))
      (node (ref "D1") (pin "A") (pinfunction "A_A") (pintype "passive"))
      (node (ref "D10") (pin "A") (pinfunction "A_A") (pintype "passive"))
      (node (ref "D101") (pin "A") (pinfunction "A_A") (pintype "passive"))
      (node (ref "D102") (pin "A") (pinfunction "A_A") (pintype "passive"))
      (node (ref "D104") (pin "A") (pinfunction "A_A") (pintype "passive"))
      (node (ref "D106") (pin "A") (pinfunction "A_A") (pintype "passive"))
      (node (ref "D109") (pin "A") (pinfunction "A_A") (pintype "passive"))
      (node (ref "D11") (pin "1") (pinfunction "A1_1") (pintype "passive"))
      (node (ref "D111") (pin "1") (pinfunction "A1_1") (pintype "passive"))
      (node (ref "D15") (pin "A") (pinfunction "A_A") (pintype "passive"))
      (node (ref "D16") (pin "A") (pinfunction "A_A") (pintype "passive"))
      (node (ref "D18") (pin "A") (pinfunction "A_A") (pintype "passive"))
      (node (ref "D2") (pin "A") (pinfunction "A_A") (pintype "passive"))
      (node (ref "D20") (pin "2") (pinfunction "A_2") (pintype "bidirectional"))
      (node (ref "D211") (pin "1") (pinfunction "A1_1") (pintype "passive"))
      (node (ref "D4") (pin "A") (pinfunction "A_A") (pintype "passive"))
      (node (ref "D5") (pin "A") (pinfunction "A_A") (pintype "passive"))
      (node (ref "D6") (pin "A") (pinfunction "A_A") (pintype "passive"))
      (node (ref "D7") (pin "A") (pinfunction "A_A") (pintype "passive"))
      (node (ref "D8") (pin "A") (pinfunction "A_A") (pintype "passive"))
      (node (ref "D9") (pin "A") (pinfunction "A_A") (pintype "passive"))
      (node (ref "GREEN") (pin "1") (pinfunction "K_1") (pintype "bidirectional"))
      (node (ref "I2C-2") (pin "2") (pinfunction "2_2") (pintype "bidirectional"))
      (node (ref "IC2-1") (pin "2") (pinfunction "2_2") (pintype "bidirectional"))
      (node (ref "LED1") (pin "2") (pinfunction "COMMON_CATHODE_2") (pintype "bidirectional"))
      (node (ref "MEGA2560PRO1") (pin "GND@1") (pinfunction "GND_GND@1") (pintype "bidirectional"))
      (node (ref "MEGA2560PRO1") (pin "GND@2") (pinfunction "GND_GND@2") (pintype "bidirectional"))
      (node (ref "MEGA2560PRO1") (pin "GND@3") (pinfunction "GND_GND@3") (pintype "bidirectional"))
      (node (ref "Q1") (pin "3") (pinfunction "E_3") (pintype "passive"))
      (node (ref "Q101") (pin "3") (pinfunction "E_3") (pintype "passive"))
      (node (ref "Q201") (pin "3") (pinfunction "E_3") (pintype "passive"))
      (node (ref "R123") (pin "1") (pinfunction "1_1") (pintype "passive"))
      (node (ref "R223") (pin "1") (pinfunction "1_1") (pintype "passive"))
      (node (ref "R23") (pin "1") (pinfunction "1_1") (pintype "passive"))
      (node (ref "R30") (pin "1") (pinfunction "1_1") (pintype "passive"))
      (node (ref "R31") (pin "2") (pinfunction "2_2") (pintype "passive"))
      (node (ref "R33") (pin "1") (pinfunction "1_1") (pintype "passive"))
      (node (ref "R39") (pin "1") (pinfunction "1_1") (pintype "passive"))
      (node (ref "R41") (pin "1") (pinfunction "1_1") (pintype "passive"))
      (node (ref "RED") (pin "1") (pinfunction "K_1") (pintype "bidirectional"))
      (node (ref "S1") (pin "1") (pinfunction "1_1") (pintype "passive"))
      (node (ref "S1") (pin "2") (pinfunction "2_2") (pintype "passive"))
      (node (ref "S1") (pin "3") (pinfunction "3_3") (pintype "passive"))
      (node (ref "S1") (pin "4") (pinfunction "4_4") (pintype "passive"))
      (node (ref "S1") (pin "5") (pinfunction "5_5") (pintype "passive"))
      (node (ref "S1") (pin "6") (pinfunction "6_6") (pintype "passive"))
      (node (ref "S1") (pin "7") (pinfunction "7_7") (pintype "passive"))
      (node (ref "S1") (pin "8") (pinfunction "8_8") (pintype "passive"))
      (node (ref "TH1") (pin "1") (pinfunction "1_1") (pintype "passive"))
      (node (ref "U1") (pin "1") (pinfunction "A1_1") (pintype "input"))
      (node (ref "U1") (pin "2") (pinfunction "A0_2") (pintype "input"))
      (node (ref "U1") (pin "7") (pinfunction "GND_7") (pintype "passive"))
      (node (ref "U2") (pin "7") (pinfunction "GND_7") (pintype "passive"))
      (node (ref "U3") (pin "3") (pinfunction "SGND_3") (pintype "bidirectional"))
      (node (ref "U3") (pin "6") (pinfunction "GND_6") (pintype "bidirectional"))
      (node (ref "U4") (pin "7") (pinfunction "VSS_7") (pintype "bidirectional"))
      (node (ref "U5") (pin "4") (pinfunction "VSS_4") (pintype "bidirectional"))
      (node (ref "U5") (pin "5") (pinfunction "DIAG_5") (pintype "bidirectional"))
      (node (ref "X2") (pin "2") (pinfunction "KL_2") (pintype "passive"))
      (node (ref "X3") (pin "6") (pinfunction "K_6") (pintype "passive"))
      (node (ref "X4") (pin "2") (pinfunction "K_2") (pintype "passive"))
      (node (ref "X4") (pin "5") (pinfunction "K_5") (pintype "passive"))
    )
    (net (code "40") (name "LED_GREEN") (class "Default")
      (node (ref "MEGA2560PRO1") (pin "A7") (pinfunction "A7_A7") (pintype "bidirectional"))
      (node (ref "R42") (pin "1") (pinfunction "1_1") (pintype "passive"))
    )
    (net (code "41") (name "LED_GREEN2") (class "Default")
      (node (ref "MEGA2560PRO1") (pin "A3") (pinfunction "A3_A3") (pintype "bidirectional"))
      (node (ref "R142") (pin "1") (pinfunction "1_1") (pintype "passive"))
    )
    (net (code "42") (name "LED_GREEN_EXT") (class "Default")
      (node (ref "D10") (pin "C") (pinfunction "C_C") (pintype "passive"))
      (node (ref "R142") (pin "2") (pinfunction "2_2") (pintype "passive"))
      (node (ref "X3") (pin "7") (pinfunction "K_7") (pintype "passive"))
    )
    (net (code "43") (name "LED_RED") (class "Default")
      (node (ref "MEGA2560PRO1") (pin "A5") (pinfunction "A5_A5") (pintype "bidirectional"))
      (node (ref "R40") (pin "1") (pinfunction "1_1") (pintype "passive"))
    )
    (net (code "44") (name "LED_RED2") (class "Default")
      (node (ref "MEGA2560PRO1") (pin "A1") (pinfunction "A1_A1") (pintype "bidirectional"))
      (node (ref "R140") (pin "1") (pinfunction "1_1") (pintype "passive"))
    )
    (net (code "45") (name "LED_RED_EXT") (class "Default")
      (node (ref "D8") (pin "C") (pinfunction "C_C") (pintype "passive"))
      (node (ref "R140") (pin "2") (pinfunction "2_2") (pintype "passive"))
      (node (ref "X3") (pin "5") (pinfunction "K_5") (pintype "passive"))
    )
    (net (code "46") (name "Net-(C29-Pad2)") (class "Default")
      (node (ref "C29") (pin "2") (pinfunction "2_2") (pintype "passive"))
      (node (ref "R41") (pin "2") (pinfunction "2_2") (pintype "passive"))
    )
    (net (code "47") (name "Net-(C31-+)") (class "Default")
      (node (ref "C31") (pin "1") (pinfunction "+_1") (pintype "passive"))
      (node (ref "D14") (pin "1") (pinfunction "K_1") (pintype "bidirectional"))
      (node (ref "U3") (pin "5") (pinfunction "ON/~{OFF}_5") (pintype "bidirectional"))
      (node (ref "U3") (pin "7") (pinfunction "VIN_7") (pintype "bidirectional"))
    )
    (net (code "48") (name "Net-(D5-PadC)") (class "Default")
      (node (ref "D5") (pin "C") (pinfunction "C_C") (pintype "passive"))
      (node (ref "MEGA2560PRO1") (pin "RX") (pinfunction "RX_RX") (pintype "bidirectional"))
    )
    (net (code "49") (name "Net-(D7-PadC)") (class "Default")
      (node (ref "D7") (pin "C") (pinfunction "C_C") (pintype "passive"))
      (node (ref "MEGA2560PRO1") (pin "TX") (pinfunction "TX_TX") (pintype "bidirectional"))
    )
    (net (code "50") (name "Net-(D11-C1A2)") (class "Default")
      (node (ref "C12") (pin "1") (pinfunction "1_1") (pintype "passive"))
      (node (ref "D11") (pin "3") (pinfunction "C1A2_3") (pintype "passive"))
      (node (ref "R23") (pin "2") (pinfunction "2_2") (pintype "passive"))
      (node (ref "R27") (pin "2") (pinfunction "2_2") (pintype "passive"))
      (node (ref "R4") (pin "2") (pinfunction "2_2") (pintype "passive"))
    )
    (net (code "51") (name "Net-(D17-K)") (class "Default")
      (node (ref "C18") (pin "1") (pinfunction "1_1") (pintype "passive"))
      (node (ref "D17") (pin "1") (pinfunction "K_1") (pintype "bidirectional"))
      (node (ref "U4") (pin "2") (pinfunction "HB_2") (pintype "bidirectional"))
    )
    (net (code "52") (name "Net-(D20-K)") (class "Default")
      (node (ref "C27") (pin "2") (pinfunction "2_2") (pintype "passive"))
      (node (ref "C29") (pin "1") (pinfunction "1_1") (pintype "passive"))
      (node (ref "D20") (pin "1") (pinfunction "K_1") (pintype "bidirectional"))
      (node (ref "L1") (pin "1") (pinfunction "P$1_1") (pintype "bidirectional"))
      (node (ref "L1") (pin "4") (pinfunction "P$1_4") (pintype "bidirectional"))
      (node (ref "U3") (pin "8") (pinfunction "LX_8") (pintype "bidirectional"))
    )
    (net (code "53") (name "Net-(D111-C1A2)") (class "Default")
      (node (ref "C112") (pin "1") (pinfunction "1_1") (pintype "passive"))
      (node (ref "D111") (pin "3") (pinfunction "C1A2_3") (pintype "passive"))
      (node (ref "R104") (pin "2") (pinfunction "2_2") (pintype "passive"))
      (node (ref "R123") (pin "2") (pinfunction "2_2") (pintype "passive"))
      (node (ref "R127") (pin "2") (pinfunction "2_2") (pintype "passive"))
    )
    (net (code "54") (name "Net-(D211-C1A2)") (class "Default")
      (node (ref "C212") (pin "1") (pinfunction "1_1") (pintype "passive"))
      (node (ref "D211") (pin "3") (pinfunction "C1A2_3") (pintype "passive"))
      (node (ref "R204") (pin "2") (pinfunction "2_2") (pintype "passive"))
      (node (ref "R223") (pin "2") (pinfunction "2_2") (pintype "passive"))
      (node (ref "R227") (pin "2") (pinfunction "2_2") (pintype "passive"))
    )
    (net (code "55") (name "Net-(GREEN-A)") (class "Default")
      (node (ref "GREEN") (pin "2") (pinfunction "A_2") (pintype "bidirectional"))
      (node (ref "LED1") (pin "3") (pinfunction "ANODE_GREEN_3") (pintype "bidirectional"))
      (node (ref "R42") (pin "2") (pinfunction "2_2") (pintype "passive"))
    )
    (net (code "56") (name "Net-(LED1-ANODE_RED)") (class "Default")
      (node (ref "LED1") (pin "1") (pinfunction "ANODE_RED_1") (pintype "bidirectional"))
      (node (ref "R40") (pin "2") (pinfunction "2_2") (pintype "passive"))
      (node (ref "RED") (pin "2") (pinfunction "A_2") (pintype "bidirectional"))
    )
    (net (code "57") (name "Net-(Q1-B)") (class "Default")
      (node (ref "Q1") (pin "1") (pinfunction "B_1") (pintype "passive"))
      (node (ref "R8") (pin "1") (pinfunction "1_1") (pintype "passive"))
    )
    (net (code "58") (name "Net-(Q2-G)") (class "Default")
      (node (ref "Q2") (pin "4") (pinfunction "G_4") (pintype "bidirectional"))
      (node (ref "R29") (pin "2") (pinfunction "2_2") (pintype "passive"))
    )
    (net (code "59") (name "Net-(Q3-G)") (class "Default")
      (node (ref "Q3") (pin "4") (pinfunction "G_4") (pintype "bidirectional"))
      (node (ref "R26") (pin "2") (pinfunction "2_2") (pintype "passive"))
    )
    (net (code "60") (name "Net-(Q101-B)") (class "Default")
      (node (ref "Q101") (pin "1") (pinfunction "B_1") (pintype "passive"))
      (node (ref "R108") (pin "1") (pinfunction "1_1") (pintype "passive"))
    )
    (net (code "61") (name "Net-(Q201-B)") (class "Default")
      (node (ref "Q201") (pin "1") (pinfunction "B_1") (pintype "passive"))
      (node (ref "R208") (pin "1") (pinfunction "1_1") (pintype "passive"))
    )
    (net (code "62") (name "Net-(U1-VBUS)") (class "Default")
      (node (ref "C4") (pin "1") (pinfunction "1_1") (pintype "passive"))
      (node (ref "D4") (pin "C") (pinfunction "C_C") (pintype "passive"))
      (node (ref "R1") (pin "1") (pinfunction "1_1") (pintype "passive"))
      (node (ref "U1") (pin "8") (pinfunction "VBUS_8") (pintype "input"))
    )
    (net (code "63") (name "Net-(U1-VIN+)") (class "Default")
      (node (ref "C2") (pin "1") (pinfunction "1_1") (pintype "passive"))
      (node (ref "R2") (pin "1") (pinfunction "1_1") (pintype "passive"))
      (node (ref "U1") (pin "10") (pinfunction "VIN+_10") (pintype "power_in"))
    )
    (net (code "64") (name "Net-(U1-VIN-)") (class "Default")
      (node (ref "C2") (pin "2") (pinfunction "2_2") (pintype "passive"))
      (node (ref "R9") (pin "1") (pinfunction "1_1") (pintype "passive"))
      (node (ref "U1") (pin "9") (pinfunction "VIN-_9") (pintype "power_in"))
    )
    (net (code "65") (name "Net-(U2-VBUS)") (class "Default")
      (node (ref "C104") (pin "1") (pinfunction "1_1") (pintype "passive"))
      (node (ref "D104") (pin "C") (pinfunction "C_C") (pintype "passive"))
      (node (ref "R101") (pin "1") (pinfunction "1_1") (pintype "passive"))
      (node (ref "U2") (pin "8") (pinfunction "VBUS_8") (pintype "input"))
    )
    (net (code "66") (name "Net-(U2-VIN+)") (class "Default")
      (node (ref "C102") (pin "1") (pinfunction "1_1") (pintype "passive"))
      (node (ref "R102") (pin "1") (pinfunction "1_1") (pintype "passive"))
      (node (ref "U2") (pin "10") (pinfunction "VIN+_10") (pintype "power_in"))
    )
    (net (code "67") (name "Net-(U2-VIN-)") (class "Default")
      (node (ref "C102") (pin "2") (pinfunction "2_2") (pintype "passive"))
      (node (ref "R109") (pin "1") (pinfunction "1_1") (pintype "passive"))
      (node (ref "U2") (pin "9") (pinfunction "VIN-_9") (pintype "power_in"))
    )
    (net (code "68") (name "Net-(U3-BST)") (class "Default")
      (node (ref "C27") (pin "1") (pinfunction "1_1") (pintype "passive"))
      (node (ref "U3") (pin "1") (pinfunction "BST_1") (pintype "bidirectional"))
    )
    (net (code "69") (name "Net-(U3-FB)") (class "Default")
      (node (ref "R39") (pin "2") (pinfunction "2_2") (pintype "passive"))
      (node (ref "R43") (pin "1") (pinfunction "1_1") (pintype "passive"))
      (node (ref "U3") (pin "4") (pinfunction "FB_4") (pintype "bidirectional"))
    )
    (net (code "70") (name "Net-(U3-VD)") (class "Default")
      (node (ref "C25") (pin "1") (pinfunction "1_1") (pintype "passive"))
      (node (ref "U3") (pin "2") (pinfunction "VD_2") (pintype "bidirectional"))
    )
    (net (code "71") (name "Net-(U4-HO)") (class "Default")
      (node (ref "R26") (pin "1") (pinfunction "1_1") (pintype "passive"))
      (node (ref "R29") (pin "1") (pinfunction "1_1") (pintype "passive"))
      (node (ref "U4") (pin "3") (pinfunction "HO_3") (pintype "bidirectional"))
    )
    (net (code "72") (name "Net-(U4-LO)") (class "Default")
      (node (ref "R19") (pin "1") (pinfunction "1_1") (pintype "passive"))
      (node (ref "U4") (pin "8") (pinfunction "LO_8") (pintype "bidirectional"))
    )
    (net (code "73") (name "Net-(U5-IN1)") (class "Default")
      (node (ref "C11") (pin "1") (pinfunction "1_1") (pintype "passive"))
      (node (ref "R7") (pin "1") (pinfunction "1_1") (pintype "passive"))
      (node (ref "U5") (pin "2") (pinfunction "IN1_2") (pintype "bidirectional"))
    )
    (net (code "74") (name "Net-(U5-RADJ)") (class "Default")
      (node (ref "R31") (pin "1") (pinfunction "1_1") (pintype "passive"))
      (node (ref "U5") (pin "1") (pinfunction "RADJ_1") (pintype "bidirectional"))
    )
    (net (code "75") (name "RX-1") (class "Default")
      (node (ref "D106") (pin "C") (pinfunction "C_C") (pintype "passive"))
      (node (ref "MEGA2560PRO1") (pin "D19") (pinfunction "D19_D19") (pintype "bidirectional"))
      (node (ref "X4") (pin "4") (pinfunction "K_4") (pintype "passive"))
    )
    (net (code "76") (name "RX-2") (class "Default")
      (node (ref "D6") (pin "C") (pinfunction "C_C") (pintype "passive"))
      (node (ref "MEGA2560PRO1") (pin "D17") (pinfunction "D17_D17") (pintype "bidirectional"))
      (node (ref "X4") (pin "1") (pinfunction "K_1") (pintype "passive"))
    )
    (net (code "77") (name "SCL") (class "Default")
      (node (ref "I2C-2") (pin "3") (pinfunction "3_3") (pintype "bidirectional"))
      (node (ref "IC2-1") (pin "3") (pinfunction "3_3") (pintype "bidirectional"))
      (node (ref "MEGA2560PRO1") (pin "D21") (pinfunction "D21_D21") (pintype "bidirectional"))
      (node (ref "R35") (pin "1") (pinfunction "1_1") (pintype "passive"))
      (node (ref "U1") (pin "5") (pinfunction "SCL_5") (pintype "input"))
      (node (ref "U2") (pin "5") (pinfunction "SCL_5") (pintype "input"))
    )
    (net (code "78") (name "SDA") (class "Default")
      (node (ref "I2C-2") (pin "4") (pinfunction "4_4") (pintype "bidirectional"))
      (node (ref "IC2-1") (pin "4") (pinfunction "4_4") (pintype "bidirectional"))
      (node (ref "MEGA2560PRO1") (pin "D20") (pinfunction "D20_D20") (pintype "bidirectional"))
      (node (ref "R37") (pin "1") (pinfunction "1_1") (pintype "passive"))
      (node (ref "U1") (pin "4") (pinfunction "SDA_4") (pintype "bidirectional"))
      (node (ref "U2") (pin "4") (pinfunction "SDA_4") (pintype "bidirectional"))
    )
    (net (code "79") (name "STATOR") (class "Default")
      (node (ref "R7") (pin "2") (pinfunction "2_2") (pintype "passive"))
      (node (ref "X1") (pin "5") (pinfunction "KL_5") (pintype "passive"))
    )
    (net (code "80") (name "STATOR_IRQ") (class "Default")
      (node (ref "MEGA2560PRO1") (pin "D2") (pinfunction "D2_D2") (pintype "bidirectional"))
      (node (ref "U4") (pin "6") (pinfunction "LI_6") (pintype "bidirectional"))
      (node (ref "U5") (pin "7") (pinfunction "OUT1_7") (pintype "bidirectional"))
    )
    (net (code "81") (name "TACH_OUT") (class "Default")
      (node (ref "R19") (pin "2") (pinfunction "2_2") (pintype "passive"))
      (node (ref "X1") (pin "6") (pinfunction "KL_6") (pintype "passive"))
    )
    (net (code "82") (name "TX-1") (class "Default")
      (node (ref "D109") (pin "C") (pinfunction "C_C") (pintype "passive"))
      (node (ref "MEGA2560PRO1") (pin "D18") (pinfunction "D18_D18") (pintype "bidirectional"))
      (node (ref "X4") (pin "6") (pinfunction "K_6") (pintype "passive"))
    )
    (net (code "83") (name "TX-2") (class "Default")
      (node (ref "D9") (pin "C") (pinfunction "C_C") (pintype "passive"))
      (node (ref "MEGA2560PRO1") (pin "D16") (pinfunction "D16_D16") (pintype "bidirectional"))
      (node (ref "X4") (pin "3") (pinfunction "K_3") (pintype "passive"))
    )
    (net (code "84") (name "VDD") (class "Default")
      (node (ref "C30") (pin "1") (pinfunction "1_1") (pintype "passive"))
      (node (ref "C32") (pin "1") (pinfunction "+_1") (pintype "passive"))
      (node (ref "D17") (pin "2") (pinfunction "A_2") (pintype "bidirectional"))
      (node (ref "L1") (pin "2") (pinfunction "P$2_2") (pintype "bidirectional"))
      (node (ref "L1") (pin "3") (pinfunction "P$2_3") (pintype "bidirectional"))
      (node (ref "MEGA2560PRO1") (pin "VIN@1") (pinfunction "VIN_VIN@1") (pintype "bidirectional"))
      (node (ref "MEGA2560PRO1") (pin "VIN@2") (pinfunction "VIN_VIN@2") (pintype "bidirectional"))
      (node (ref "R43") (pin "2") (pinfunction "2_2") (pintype "passive"))
      (node (ref "TP-VDD") (pin "TP") (pinfunction "TP_TP") (pintype "input"))
      (node (ref "U4") (pin "1") (pinfunction "VDD_1") (pintype "bidirectional"))
    )
    (net (code "85") (name "unconnected-(FIDUCIAL1-PadP$1)") (class "Default")
      (node (ref "FIDUCIAL1") (pin "P$1") (pinfunction "P$1_P$1") (pintype "bidirectional"))
    )
    (net (code "86") (name "unconnected-(FIDUCIAL2-PadP$1)") (class "Default")
      (node (ref "FIDUCIAL2") (pin "P$1") (pinfunction "P$1_P$1") (pintype "bidirectional"))
    )
    (net (code "87") (name "unconnected-(MEGA2560PRO1-3V3-Pad3V3@1)") (class "Default")
      (node (ref "MEGA2560PRO1") (pin "3V3@1") (pinfunction "3V3_3V3@1") (pintype "bidirectional"))
    )
    (net (code "88") (name "unconnected-(MEGA2560PRO1-3V3-Pad3V3@2)") (class "Default")
      (node (ref "MEGA2560PRO1") (pin "3V3@2") (pinfunction "3V3_3V3@2") (pintype "bidirectional"))
    )
    (net (code "89") (name "unconnected-(MEGA2560PRO1-PadA4)") (class "Default")
      (node (ref "MEGA2560PRO1") (pin "A4") (pinfunction "A4_A4") (pintype "bidirectional"))
    )
    (net (code "90") (name "unconnected-(MEGA2560PRO1-PadA6)") (class "Default")
      (node (ref "MEGA2560PRO1") (pin "A6") (pinfunction "A6_A6") (pintype "bidirectional"))
    )
    (net (code "91") (name "unconnected-(MEGA2560PRO1-PadA9)") (class "Default")
      (node (ref "MEGA2560PRO1") (pin "A9") (pinfunction "A9_A9") (pintype "bidirectional"))
    )
    (net (code "92") (name "unconnected-(MEGA2560PRO1-PadA10)") (class "Default")
      (node (ref "MEGA2560PRO1") (pin "A10") (pinfunction "A10_A10") (pintype "bidirectional"))
    )
    (net (code "93") (name "unconnected-(MEGA2560PRO1-PadA11)") (class "Default")
      (node (ref "MEGA2560PRO1") (pin "A11") (pinfunction "A11_A11") (pintype "bidirectional"))
    )
    (net (code "94") (name "unconnected-(MEGA2560PRO1-PadA12)") (class "Default")
      (node (ref "MEGA2560PRO1") (pin "A12") (pinfunction "A12_A12") (pintype "bidirectional"))
    )
    (net (code "95") (name "unconnected-(MEGA2560PRO1-PadA13)") (class "Default")
      (node (ref "MEGA2560PRO1") (pin "A13") (pinfunction "A13_A13") (pintype "bidirectional"))
    )
    (net (code "96") (name "unconnected-(MEGA2560PRO1-PadA14)") (class "Default")
      (node (ref "MEGA2560PRO1") (pin "A14") (pinfunction "A14_A14") (pintype "bidirectional"))
    )
    (net (code "97") (name "unconnected-(MEGA2560PRO1-PadA15)") (class "Default")
      (node (ref "MEGA2560PRO1") (pin "A15") (pinfunction "A15_A15") (pintype "bidirectional"))
    )
    (net (code "98") (name "unconnected-(MEGA2560PRO1-PadAREF)") (class "Default")
      (node (ref "MEGA2560PRO1") (pin "AREF") (pinfunction "AREF_AREF") (pintype "bidirectional"))
    )
    (net (code "99") (name "unconnected-(MEGA2560PRO1-PadD15)") (class "Default")
      (node (ref "MEGA2560PRO1") (pin "D15") (pinfunction "D15_D15") (pintype "bidirectional"))
    )
    (net (code "100") (name "unconnected-(MEGA2560PRO1-PadD22)") (class "Default")
      (node (ref "MEGA2560PRO1") (pin "D22") (pinfunction "D22_D22") (pintype "bidirectional"))
    )
    (net (code "101") (name "unconnected-(MEGA2560PRO1-PadD23)") (class "Default")
      (node (ref "MEGA2560PRO1") (pin "D23") (pinfunction "D23_D23") (pintype "bidirectional"))
    )
    (net (code "102") (name "unconnected-(MEGA2560PRO1-PadD24)") (class "Default")
      (node (ref "MEGA2560PRO1") (pin "D24") (pinfunction "D24_D24") (pintype "bidirectional"))
    )
    (net (code "103") (name "unconnected-(MEGA2560PRO1-PadD25)") (class "Default")
      (node (ref "MEGA2560PRO1") (pin "D25") (pinfunction "D25_D25") (pintype "bidirectional"))
    )
    (net (code "104") (name "unconnected-(MEGA2560PRO1-PadD26)") (class "Default")
      (node (ref "MEGA2560PRO1") (pin "D26") (pinfunction "D26_D26") (pintype "bidirectional"))
    )
    (net (code "105") (name "unconnected-(MEGA2560PRO1-PadD28)") (class "Default")
      (node (ref "MEGA2560PRO1") (pin "D28") (pinfunction "D28_D28") (pintype "bidirectional"))
    )
    (net (code "106") (name "unconnected-(MEGA2560PRO1-PadD30)") (class "Default")
      (node (ref "MEGA2560PRO1") (pin "D30") (pinfunction "D30_D30") (pintype "bidirectional"))
    )
    (net (code "107") (name "unconnected-(MEGA2560PRO1-PadD32)") (class "Default")
      (node (ref "MEGA2560PRO1") (pin "D32") (pinfunction "D32_D32") (pintype "bidirectional"))
    )
    (net (code "108") (name "unconnected-(MEGA2560PRO1-PadD33)") (class "Default")
      (node (ref "MEGA2560PRO1") (pin "D33") (pinfunction "D33_D33") (pintype "bidirectional"))
    )
    (net (code "109") (name "unconnected-(MEGA2560PRO1-PadD34)") (class "Default")
      (node (ref "MEGA2560PRO1") (pin "D34") (pinfunction "D34_D34") (pintype "bidirectional"))
    )
    (net (code "110") (name "unconnected-(MEGA2560PRO1-PadD35)") (class "Default")
      (node (ref "MEGA2560PRO1") (pin "D35") (pinfunction "D35_D35") (pintype "bidirectional"))
    )
    (net (code "111") (name "unconnected-(MEGA2560PRO1-PadD36)") (class "Default")
      (node (ref "MEGA2560PRO1") (pin "D36") (pinfunction "D36_D36") (pintype "bidirectional"))
    )
    (net (code "112") (name "unconnected-(MEGA2560PRO1-PadD37)") (class "Default")
      (node (ref "MEGA2560PRO1") (pin "D37") (pinfunction "D37_D37") (pintype "bidirectional"))
    )
    (net (code "113") (name "unconnected-(MEGA2560PRO1-PadD38)") (class "Default")
      (node (ref "MEGA2560PRO1") (pin "D38") (pinfunction "D38_D38") (pintype "bidirectional"))
    )
    (net (code "114") (name "unconnected-(MEGA2560PRO1-PadD39)") (class "Default")
      (node (ref "MEGA2560PRO1") (pin "D39") (pinfunction "D39_D39") (pintype "bidirectional"))
    )
    (net (code "115") (name "unconnected-(MEGA2560PRO1-PadD40)") (class "Default")
      (node (ref "MEGA2560PRO1") (pin "D40") (pinfunction "D40_D40") (pintype "bidirectional"))
    )
    (net (code "116") (name "unconnected-(MEGA2560PRO1-PadD41)") (class "Default")
      (node (ref "MEGA2560PRO1") (pin "D41") (pinfunction "D41_D41") (pintype "bidirectional"))
    )
    (net (code "117") (name "unconnected-(MEGA2560PRO1-PadD42)") (class "Default")
      (node (ref "MEGA2560PRO1") (pin "D42") (pinfunction "D42_D42") (pintype "bidirectional"))
    )
    (net (code "118") (name "unconnected-(MEGA2560PRO1-PadD43)") (class "Default")
      (node (ref "MEGA2560PRO1") (pin "D43") (pinfunction "D43_D43") (pintype "bidirectional"))
    )
    (net (code "119") (name "unconnected-(MEGA2560PRO1-PadD44)") (class "Default")
      (node (ref "MEGA2560PRO1") (pin "D44") (pinfunction "D44_D44") (pintype "bidirectional"))
    )
    (net (code "120") (name "unconnected-(MEGA2560PRO1-PadD45)") (class "Default")
      (node (ref "MEGA2560PRO1") (pin "D45") (pinfunction "D45_D45") (pintype "bidirectional"))
    )
    (net (code "121") (name "unconnected-(MEGA2560PRO1-PadD46)") (class "Default")
      (node (ref "MEGA2560PRO1") (pin "D46") (pinfunction "D46_D46") (pintype "bidirectional"))
    )
    (net (code "122") (name "unconnected-(MEGA2560PRO1-PadD47)") (class "Default")
      (node (ref "MEGA2560PRO1") (pin "D47") (pinfunction "D47_D47") (pintype "bidirectional"))
    )
    (net (code "123") (name "unconnected-(MEGA2560PRO1-PadD48)") (class "Default")
      (node (ref "MEGA2560PRO1") (pin "D48") (pinfunction "D48_D48") (pintype "bidirectional"))
    )
    (net (code "124") (name "unconnected-(MEGA2560PRO1-PadD49)") (class "Default")
      (node (ref "MEGA2560PRO1") (pin "D49") (pinfunction "D49_D49") (pintype "bidirectional"))
    )
    (net (code "125") (name "unconnected-(MEGA2560PRO1-PadD50)") (class "Default")
      (node (ref "MEGA2560PRO1") (pin "D50") (pinfunction "D50_D50") (pintype "bidirectional"))
    )
    (net (code "126") (name "unconnected-(MEGA2560PRO1-PadD51)") (class "Default")
      (node (ref "MEGA2560PRO1") (pin "D51") (pinfunction "D51_D51") (pintype "bidirectional"))
    )
    (net (code "127") (name "unconnected-(MEGA2560PRO1-PadD52)") (class "Default")
      (node (ref "MEGA2560PRO1") (pin "D52") (pinfunction "D52_D52") (pintype "bidirectional"))
    )
    (net (code "128") (name "unconnected-(MEGA2560PRO1-PadD53)") (class "Default")
      (node (ref "MEGA2560PRO1") (pin "D53") (pinfunction "D53_D53") (pintype "bidirectional"))
    )
    (net (code "129") (name "unconnected-(MEGA2560PRO1-PadMISO)") (class "Default")
      (node (ref "MEGA2560PRO1") (pin "MISO") (pinfunction "MISO_MISO") (pintype "bidirectional"))
    )
    (net (code "130") (name "unconnected-(MEGA2560PRO1-PadMOSI)") (class "Default")
      (node (ref "MEGA2560PRO1") (pin "MOSI") (pinfunction "MOSI_MOSI") (pintype "bidirectional"))
    )
    (net (code "131") (name "unconnected-(MEGA2560PRO1-PadRESET)") (class "Default")
      (node (ref "MEGA2560PRO1") (pin "RESET") (pinfunction "RESET_RESET") (pintype "bidirectional"))
    )
    (net (code "132") (name "unconnected-(MEGA2560PRO1-PadRST)") (class "Default")
      (node (ref "MEGA2560PRO1") (pin "RST") (pinfunction "RST_RST") (pintype "bidirectional"))
    )
    (net (code "133") (name "unconnected-(MEGA2560PRO1-PadSCK)") (class "Default")
      (node (ref "MEGA2560PRO1") (pin "SCK") (pinfunction "SCK_SCK") (pintype "bidirectional"))
    )
    (net (code "134") (name "unconnected-(U1-ALERT-Pad3)") (class "Default")
      (node (ref "U1") (pin "3") (pinfunction "ALERT_3") (pintype "output"))
    )
    (net (code "135") (name "unconnected-(U2-ALERT-Pad3)") (class "Default")
      (node (ref "U2") (pin "3") (pinfunction "ALERT_3") (pintype "output"))
    )
    (net (code "136") (name "unconnected-(U5-IN2-Pad3)") (class "Default")
      (node (ref "U5") (pin "3") (pinfunction "IN2_3") (pintype "no_connect"))
    )
    (net (code "137") (name "unconnected-(U5-OUT2-Pad6)") (class "Default")
      (node (ref "U5") (pin "6") (pinfunction "OUT2_6") (pintype "no_connect"))
    )
  )
)
